# SX126x.net
KiCad netlist of a schematic drawn in Altium Designer
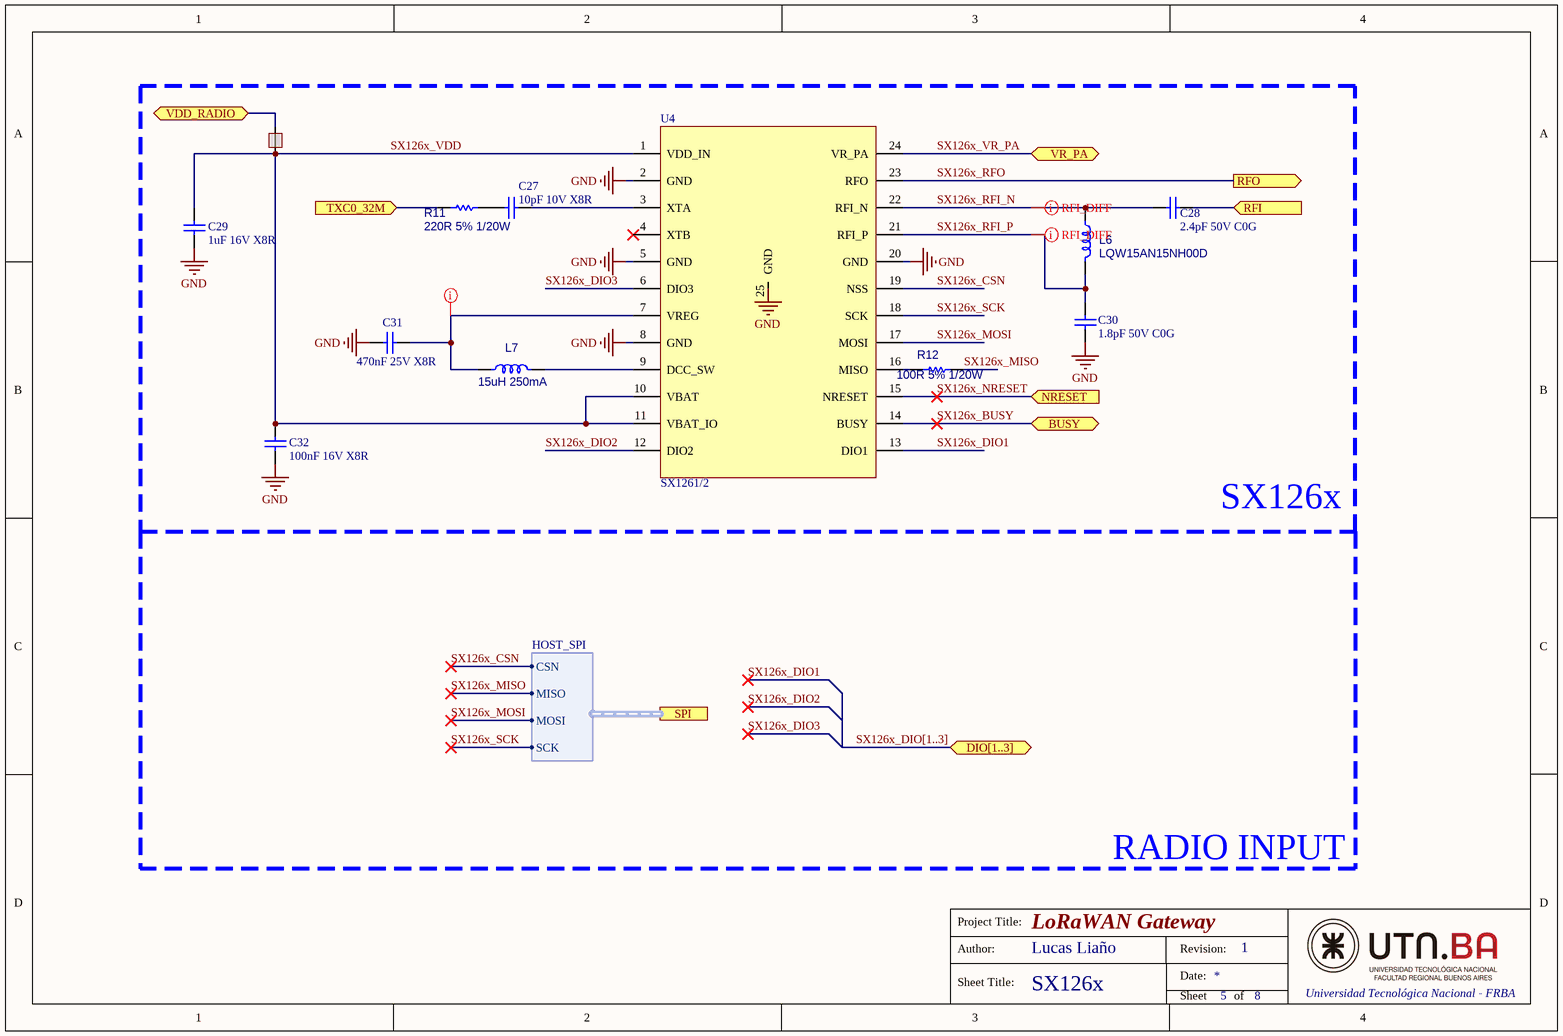
[diagram p0: SX126x.SchDoc]

(export (version "E")
  (design (tool "Eeschema 10.0.6"))
  (components
    (comp (ref "C27")
      (value "10pF 10V X8R")
      (footprint "C_0603")
      (description "Capacitor")
      (fields (field (name "MPN") "C0603X100J8HACAUTO") (field (name "MANUFACTURER") "KEMET"))
      (libsource (lib "lorawan_gateway") (part "Cap"))
    )
    (comp (ref "C28")
      (value "2.4pF 50V C0G")
      (footprint "C_0603")
      (description "Capacitor")
      (fields (field (name "MPN") "GJM0335C1H2R4WB01") (field (name "MANUFACTURER") "Murata Electronics"))
      (libsource (lib "lorawan_gateway") (part "Cap"))
    )
    (comp (ref "C29")
      (value "1uF 16V X8R")
      (footprint "C_0603")
      (description "Capacitor")
      (fields (field (name "MPN") "CGA4J3X8R1C105K125AB") (field (name "MANUFACTURER") "TDK Corporation"))
      (libsource (lib "lorawan_gateway") (part "Cap"))
    )
    (comp (ref "C30")
      (value "1.8pF 50V C0G")
      (footprint "C_0603")
      (description "Capacitor")
      (fields (field (name "MPN") "GJM0335C1H1R8WB01") (field (name "MANUFACTURER") "Murata Electronics"))
      (libsource (lib "lorawan_gateway") (part "Cap"))
    )
    (comp (ref "C31")
      (value "470nF 25V X8R")
      (footprint "C_0603")
      (description "Capacitor")
      (fields (field (name "MPN") "VJ0603H472JXXAC") (field (name "MANUFACTURER") "Vishay"))
      (libsource (lib "lorawan_gateway") (part "Cap"))
    )
    (comp (ref "C32")
      (value "100nF 16V X8R")
      (footprint "C_0603")
      (description "Capacitor")
      (fields (field (name "MPN") "C1206C104K4HACAUTO") (field (name "MANUFACTURER") "KEMET"))
      (libsource (lib "lorawan_gateway") (part "Cap"))
    )
    (comp (ref "L6")
      (value "LQW15AN15NH00D")
      (footprint "L_0402")
      (description "Inductor")
      (libsource (lib "lorawan_gateway") (part "IND"))
    )
    (comp (ref "L7")
      (value "15uH 250mA")
      (footprint "0805[2012]")
      (description "FIXED IND 15UH 250MA 950MOHM SMD")
      (fields (field (name "MANUFACTURER") "TDK Corporation") (field (name "MPN") "MLZ2012M150WT000"))
      (libsource (lib "lorawan_gateway") (part "IND"))
    )
    (comp (ref "NT17")
      (value "NT")
      (footprint "NTIE24")
      (description "NET_TIE")
      (libsource (lib "lorawan_gateway") (part "NTIE"))
    )
    (comp (ref "R11")
      (value "220R 5% 1/20W")
      (footprint "0603[1608]")
      (description "Resistor")
      (fields
        (field (name "MANUFACTURER") "Panasonic Electronic Components")
        (field (name "MPN") "ERJ-1GNJ221C")
      )
      (libsource (lib "lorawan_gateway") (part "Res"))
    )
    (comp (ref "R12")
      (value "100R 5% 1/20W")
      (footprint "0603[1608]")
      (description "Resistor")
      (fields (field (name "MANUFACTURER") "Stackpole") (field (name "MPN") "RMCF0201JT100R"))
      (libsource (lib "lorawan_gateway") (part "Res"))
    )
    (comp (ref "U4")
      (value "SX1261/2")
      (footprint "vqfn24_4x4mm")
      (description "SX1261/2 - Ultra low power RF transceiver")
      (fields (field (name "MANUFACTURER") "Semtech") (field (name "MPN") "SX1261IMLTRT"))
      (libsource (lib "lorawan_gateway") (part "SX126x"))
    )
  )
  (nets
    (net (code "2") (name "/BUSY") (class "Default")
      (node (ref "U4") (pin "14") (pinfunction "BUSY_14") (pintype "passive"))
    )
    (net (code "3") (name "/NRESET") (class "Default")
      (node (ref "U4") (pin "15") (pinfunction "NRESET_15") (pintype "passive"))
    )
    (net (code "4") (name "/RFI") (class "Default")
      (node (ref "C28") (pin "2") (pinfunction "2_2") (pintype "passive"))
    )
    (net (code "6") (name "/SX126x_CSN") (class "Default")
      (node (ref "U4") (pin "19") (pinfunction "NSS_19") (pintype "passive"))
    )
    (net (code "7") (name "/SX126x_DIO1") (class "Default")
      (node (ref "U4") (pin "13") (pinfunction "DIO1_13") (pintype "passive+no_connect"))
    )
    (net (code "8") (name "/SX126x_DIO2") (class "Default")
      (node (ref "U4") (pin "12") (pinfunction "DIO2_12") (pintype "passive+no_connect"))
    )
    (net (code "9") (name "/SX126x_DIO3") (class "Default")
      (node (ref "U4") (pin "6") (pinfunction "DIO3_6") (pintype "passive+no_connect"))
    )
    (net (code "11") (name "/SX126x_MISO") (class "Default")
      (node (ref "R12") (pin "1") (pinfunction "1_1") (pintype "passive+no_connect"))
    )
    (net (code "12") (name "/SX126x_MOSI") (class "Default")
      (node (ref "U4") (pin "17") (pinfunction "MOSI_17") (pintype "passive"))
    )
    (net (code "14") (name "/SX126x_RFI_N") (class "Default")
      (node (ref "C28") (pin "1") (pinfunction "1_1") (pintype "passive"))
      (node (ref "L6") (pin "1") (pinfunction "1_1") (pintype "passive"))
      (node (ref "U4") (pin "22") (pinfunction "RFI_N_22") (pintype "passive"))
    )
    (net (code "15") (name "/SX126x_RFI_P") (class "Default")
      (node (ref "C30") (pin "1") (pinfunction "1_1") (pintype "passive"))
      (node (ref "L6") (pin "2") (pinfunction "2_2") (pintype "passive"))
      (node (ref "U4") (pin "21") (pinfunction "RFI_P_21") (pintype "passive"))
    )
    (net (code "16") (name "/SX126x_RFO") (class "Default")
      (node (ref "U4") (pin "23") (pinfunction "RFO_23") (pintype "passive"))
    )
    (net (code "17") (name "/SX126x_SCK") (class "Default")
      (node (ref "U4") (pin "18") (pinfunction "SCK_18") (pintype "passive"))
    )
    (net (code "18") (name "/SX126x_VDD") (class "Default")
      (node (ref "C29") (pin "1") (pinfunction "1_1") (pintype "passive"))
      (node (ref "C32") (pin "1") (pinfunction "1_1") (pintype "passive"))
      (node (ref "NT17") (pin "1") (pinfunction "1_1") (pintype "passive"))
      (node (ref "U4") (pin "1") (pinfunction "VDD_IN_1") (pintype "power_in"))
      (node (ref "U4") (pin "10") (pinfunction "VBAT_10") (pintype "power_in"))
      (node (ref "U4") (pin "11") (pinfunction "VBAT_IO_11") (pintype "power_in"))
    )
    (net (code "19") (name "/SX126x_VR_PA") (class "Default")
      (node (ref "U4") (pin "24") (pinfunction "VR_PA_24") (pintype "passive"))
    )
    (net (code "20") (name "/TXC0_32M") (class "Default")
      (node (ref "R11") (pin "1") (pinfunction "1_1") (pintype "passive"))
    )
    (net (code "21") (name "/VDD_RADIO") (class "Default")
      (node (ref "NT17") (pin "2") (pinfunction "2_2") (pintype "passive"))
    )
    (net (code "23") (name "GND") (class "Default")
      (node (ref "C29") (pin "2") (pinfunction "2_2") (pintype "passive"))
      (node (ref "C30") (pin "2") (pinfunction "2_2") (pintype "passive"))
      (node (ref "C31") (pin "2") (pinfunction "2_2") (pintype "passive"))
      (node (ref "C32") (pin "2") (pinfunction "2_2") (pintype "passive"))
      (node (ref "U4") (pin "2") (pinfunction "GND_2") (pintype "passive"))
      (node (ref "U4") (pin "20") (pinfunction "GND_20") (pintype "passive"))
      (node (ref "U4") (pin "25") (pinfunction "GND_25") (pintype "passive"))
      (node (ref "U4") (pin "5") (pinfunction "GND_5") (pintype "passive"))
      (node (ref "U4") (pin "8") (pinfunction "GND_8") (pintype "passive"))
    )
    (net (code "24") (name "Net-(C27-Pad2)") (class "Default")
      (node (ref "C27") (pin "2") (pinfunction "2_2") (pintype "passive"))
      (node (ref "R11") (pin "2") (pinfunction "2_2") (pintype "passive"))
    )
    (net (code "25") (name "Net-(U4-DCC_SW)") (class "Default")
      (node (ref "L7") (pin "2") (pinfunction "2_2") (pintype "passive"))
      (node (ref "U4") (pin "9") (pinfunction "DCC_SW_9") (pintype "power_in"))
    )
    (net (code "26") (name "Net-(U4-MISO)") (class "Default")
      (node (ref "R12") (pin "2") (pinfunction "2_2") (pintype "passive"))
      (node (ref "U4") (pin "16") (pinfunction "MISO_16") (pintype "passive"))
    )
    (net (code "27") (name "Net-(U4-VREG)") (class "Default")
      (node (ref "C31") (pin "1") (pinfunction "1_1") (pintype "passive"))
      (node (ref "L7") (pin "1") (pinfunction "1_1") (pintype "passive"))
      (node (ref "U4") (pin "7") (pinfunction "VREG_7") (pintype "power_in"))
    )
    (net (code "28") (name "Net-(U4-XTA)") (class "Default")
      (node (ref "C27") (pin "1") (pinfunction "1_1") (pintype "passive"))
      (node (ref "U4") (pin "3") (pinfunction "XTA_3") (pintype "passive"))
    )
    (net (code "29") (name "unconnected-(U4-XTB-Pad4)") (class "Default")
      (node (ref "U4") (pin "4") (pinfunction "XTB_4") (pintype "passive+no_connect"))
    )
  )
)
